# LV25-P_850Vdc_ADC.net
KiCad netlist of a schematic drawn in Altium Designer
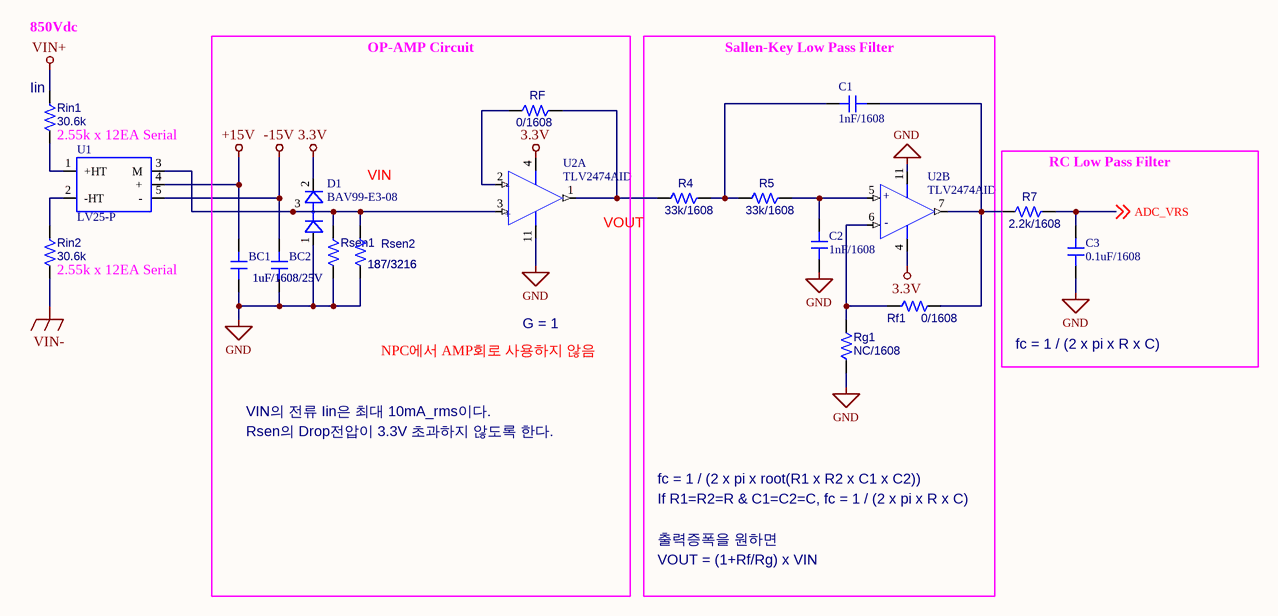
[diagram p0: LV25-P 850Vdc ADC 센싱회로.SchDoc]

(export (version "E")
  (design (tool "Eeschema 10.0.6"))
  (components
    (comp (ref "BC1")
      (value "1uF/1608/25V")
      (footprint "C-1608")
      (libsource (lib "*") (part "CAPACITOR NON-POL_1"))
    )
    (comp (ref "BC2")
      (value "1uF/1608/25V")
      (footprint "C-1608")
      (libsource (lib "*") (part "CAPACITOR NON-POL_1"))
    )
    (comp (ref "C1")
      (value "1nF/1608")
      (footprint "C-1608")
      (libsource (lib "*") (part "CAPACITOR NON-POL_1"))
    )
    (comp (ref "C2")
      (value "1nF/1608")
      (footprint "C-1608")
      (libsource (lib "*") (part "CAPACITOR NON-POL_1"))
    )
    (comp (ref "C3")
      (value "0.1uF/1608")
      (footprint "C-1608")
      (libsource (lib "*") (part "CAPACITOR NON-POL_1"))
    )
    (comp (ref "D1")
      (value "BAV99-E3-08")
      (footprint "SOT-23")
      (description "DIODE ARRAY GP 70V 150MA SOT23")
      (libsource (lib "Schlib1_BAV99") (part "BAV99-E3-08"))
    )
    (comp (ref "R4") (value "33k/1608") (footprint "R-1608") (libsource (lib "*") (part "R_Dup1")))
    (comp (ref "R5") (value "33k/1608") (footprint "R-1608") (libsource (lib "*") (part "R_Dup1")))
    (comp (ref "R7") (value "2.2k/1608") (footprint "R-1608") (libsource (lib "*") (part "R_Dup1")))
    (comp (ref "RF") (value "0/1608") (footprint "R-1608") (libsource (lib "*") (part "R_Dup1")))
    (comp (ref "Rf1") (value "0/1608") (footprint "R-1608") (libsource (lib "*") (part "R_Dup1")))
    (comp (ref "Rg1") (value "NC/1608") (footprint "R-1608") (libsource (lib "*") (part "R_Dup1")))
    (comp (ref "Rin1") (value "30.6k") (footprint "R-1608") (libsource (lib "*") (part "R_Dup1")))
    (comp (ref "Rin2") (value "30.6k") (footprint "R-1608") (libsource (lib "*") (part "R_Dup1")))
    (comp (ref "Rsen1") (value "187/3216") (footprint "R-1608") (libsource (lib "*") (part "R_Dup1")))
    (comp (ref "Rsen2") (value "187/3216") (footprint "R-1608") (libsource (lib "*") (part "R_Dup1")))
    (comp (ref "U1") (value "LV25-P") (libsource (lib "SysInTeck_SchLib1") (part "LV25-P")))
    (comp (ref "U2") (value "TLV2474AID") (footprint "SO-14") (libsource (lib "*") (part "OPA4336_1")))
  )
  (nets
    (net (code "1") (name "+15V") (class "Default")
      (node (ref "BC1") (pin "1") (pinfunction "1_1") (pintype "passive"))
      (node (ref "U1") (pin "4") (pinfunction "+_4") (pintype "passive"))
    )
    (net (code "2") (name "-15V") (class "Default")
      (node (ref "BC2") (pin "1") (pinfunction "1_1") (pintype "passive"))
      (node (ref "U1") (pin "5") (pinfunction "-_5") (pintype "passive"))
    )
    (net (code "3") (name "3.3V") (class "Default")
      (node (ref "D1") (pin "2") (pinfunction "2_2") (pintype "passive"))
      (node (ref "U2") (pin "4") (pinfunction "+VCC_4") (pintype "power_in"))
    )
    (net (code "4") (name "ADC_VRS") (class "Default")
      (node (ref "C3") (pin "1") (pinfunction "1_1") (pintype "passive"))
      (node (ref "R7") (pin "1") (pinfunction "1_1") (pintype "passive"))
    )
    (net (code "5") (name "GND") (class "Default")
      (node (ref "BC1") (pin "2") (pinfunction "2_2") (pintype "passive"))
      (node (ref "BC2") (pin "2") (pinfunction "2_2") (pintype "passive"))
      (node (ref "C2") (pin "2") (pinfunction "2_2") (pintype "passive"))
      (node (ref "C3") (pin "2") (pinfunction "2_2") (pintype "passive"))
      (node (ref "D1") (pin "1") (pinfunction "1_1") (pintype "passive"))
      (node (ref "Rg1") (pin "1") (pinfunction "1_1") (pintype "passive"))
      (node (ref "Rsen1") (pin "2") (pinfunction "2_2") (pintype "passive"))
      (node (ref "Rsen2") (pin "2") (pinfunction "2_2") (pintype "passive"))
      (node (ref "U2") (pin "11") (pinfunction "-VCC_11") (pintype "power_in"))
    )
    (net (code "6") (name "Net-(C1-Pad1)") (class "Default")
      (node (ref "C1") (pin "1") (pinfunction "1_1") (pintype "passive"))
      (node (ref "R4") (pin "1") (pinfunction "1_1") (pintype "passive"))
      (node (ref "R5") (pin "2") (pinfunction "2_2") (pintype "passive"))
    )
    (net (code "7") (name "Net-(U1-+HT)") (class "Default")
      (node (ref "Rin1") (pin "2") (pinfunction "2_2") (pintype "passive"))
      (node (ref "U1") (pin "1") (pinfunction "+HT_1") (pintype "passive"))
    )
    (net (code "8") (name "Net-(U1--HT)") (class "Default")
      (node (ref "Rin2") (pin "1") (pinfunction "1_1") (pintype "passive"))
      (node (ref "U1") (pin "2") (pinfunction "-HT_2") (pintype "passive"))
    )
    (net (code "9") (name "Net-(U1-M)") (class "Default")
      (node (ref "D1") (pin "3") (pinfunction "3_3") (pintype "passive"))
      (node (ref "Rsen1") (pin "1") (pinfunction "1_1") (pintype "passive"))
      (node (ref "Rsen2") (pin "1") (pinfunction "1_1") (pintype "passive"))
      (node (ref "U1") (pin "3") (pinfunction "M_3") (pintype "passive"))
      (node (ref "U2") (pin "3") (pinfunction "+IN_3") (pintype "input"))
    )
    (net (code "10") (name "Net-(U2A--IN)") (class "Default")
      (node (ref "RF") (pin "2") (pinfunction "2_2") (pintype "passive"))
      (node (ref "U2") (pin "2") (pinfunction "-IN_2") (pintype "input"))
    )
    (net (code "11") (name "Net-(U2A-OUT)") (class "Default")
      (node (ref "R4") (pin "2") (pinfunction "2_2") (pintype "passive"))
      (node (ref "RF") (pin "1") (pinfunction "1_1") (pintype "passive"))
      (node (ref "U2") (pin "1") (pinfunction "OUT_1") (pintype "output"))
    )
    (net (code "12") (name "Net-(U2B-+IN)") (class "Default")
      (node (ref "C2") (pin "1") (pinfunction "1_1") (pintype "passive"))
      (node (ref "R5") (pin "1") (pinfunction "1_1") (pintype "passive"))
      (node (ref "U2") (pin "5") (pinfunction "+IN_5") (pintype "input"))
    )
    (net (code "13") (name "Net-(U2B--IN)") (class "Default")
      (node (ref "Rf1") (pin "1") (pinfunction "1_1") (pintype "passive"))
      (node (ref "Rg1") (pin "2") (pinfunction "2_2") (pintype "passive"))
      (node (ref "U2") (pin "6") (pinfunction "-IN_6") (pintype "input"))
    )
    (net (code "14") (name "Net-(U2B-OUT)") (class "Default")
      (node (ref "C1") (pin "2") (pinfunction "2_2") (pintype "passive"))
      (node (ref "R7") (pin "2") (pinfunction "2_2") (pintype "passive"))
      (node (ref "Rf1") (pin "2") (pinfunction "2_2") (pintype "passive"))
      (node (ref "U2") (pin "7") (pinfunction "OUT_7") (pintype "output"))
    )
    (net (code "15") (name "VIN+") (class "Default")
      (node (ref "Rin1") (pin "1") (pinfunction "1_1") (pintype "passive"))
    )
    (net (code "16") (name "VIN-") (class "Default")
      (node (ref "Rin2") (pin "2") (pinfunction "2_2") (pintype "passive"))
    )
  )
)
